# TJMakes_Template.net
KiCad netlist of a schematic drawn in EasyEDA Pro
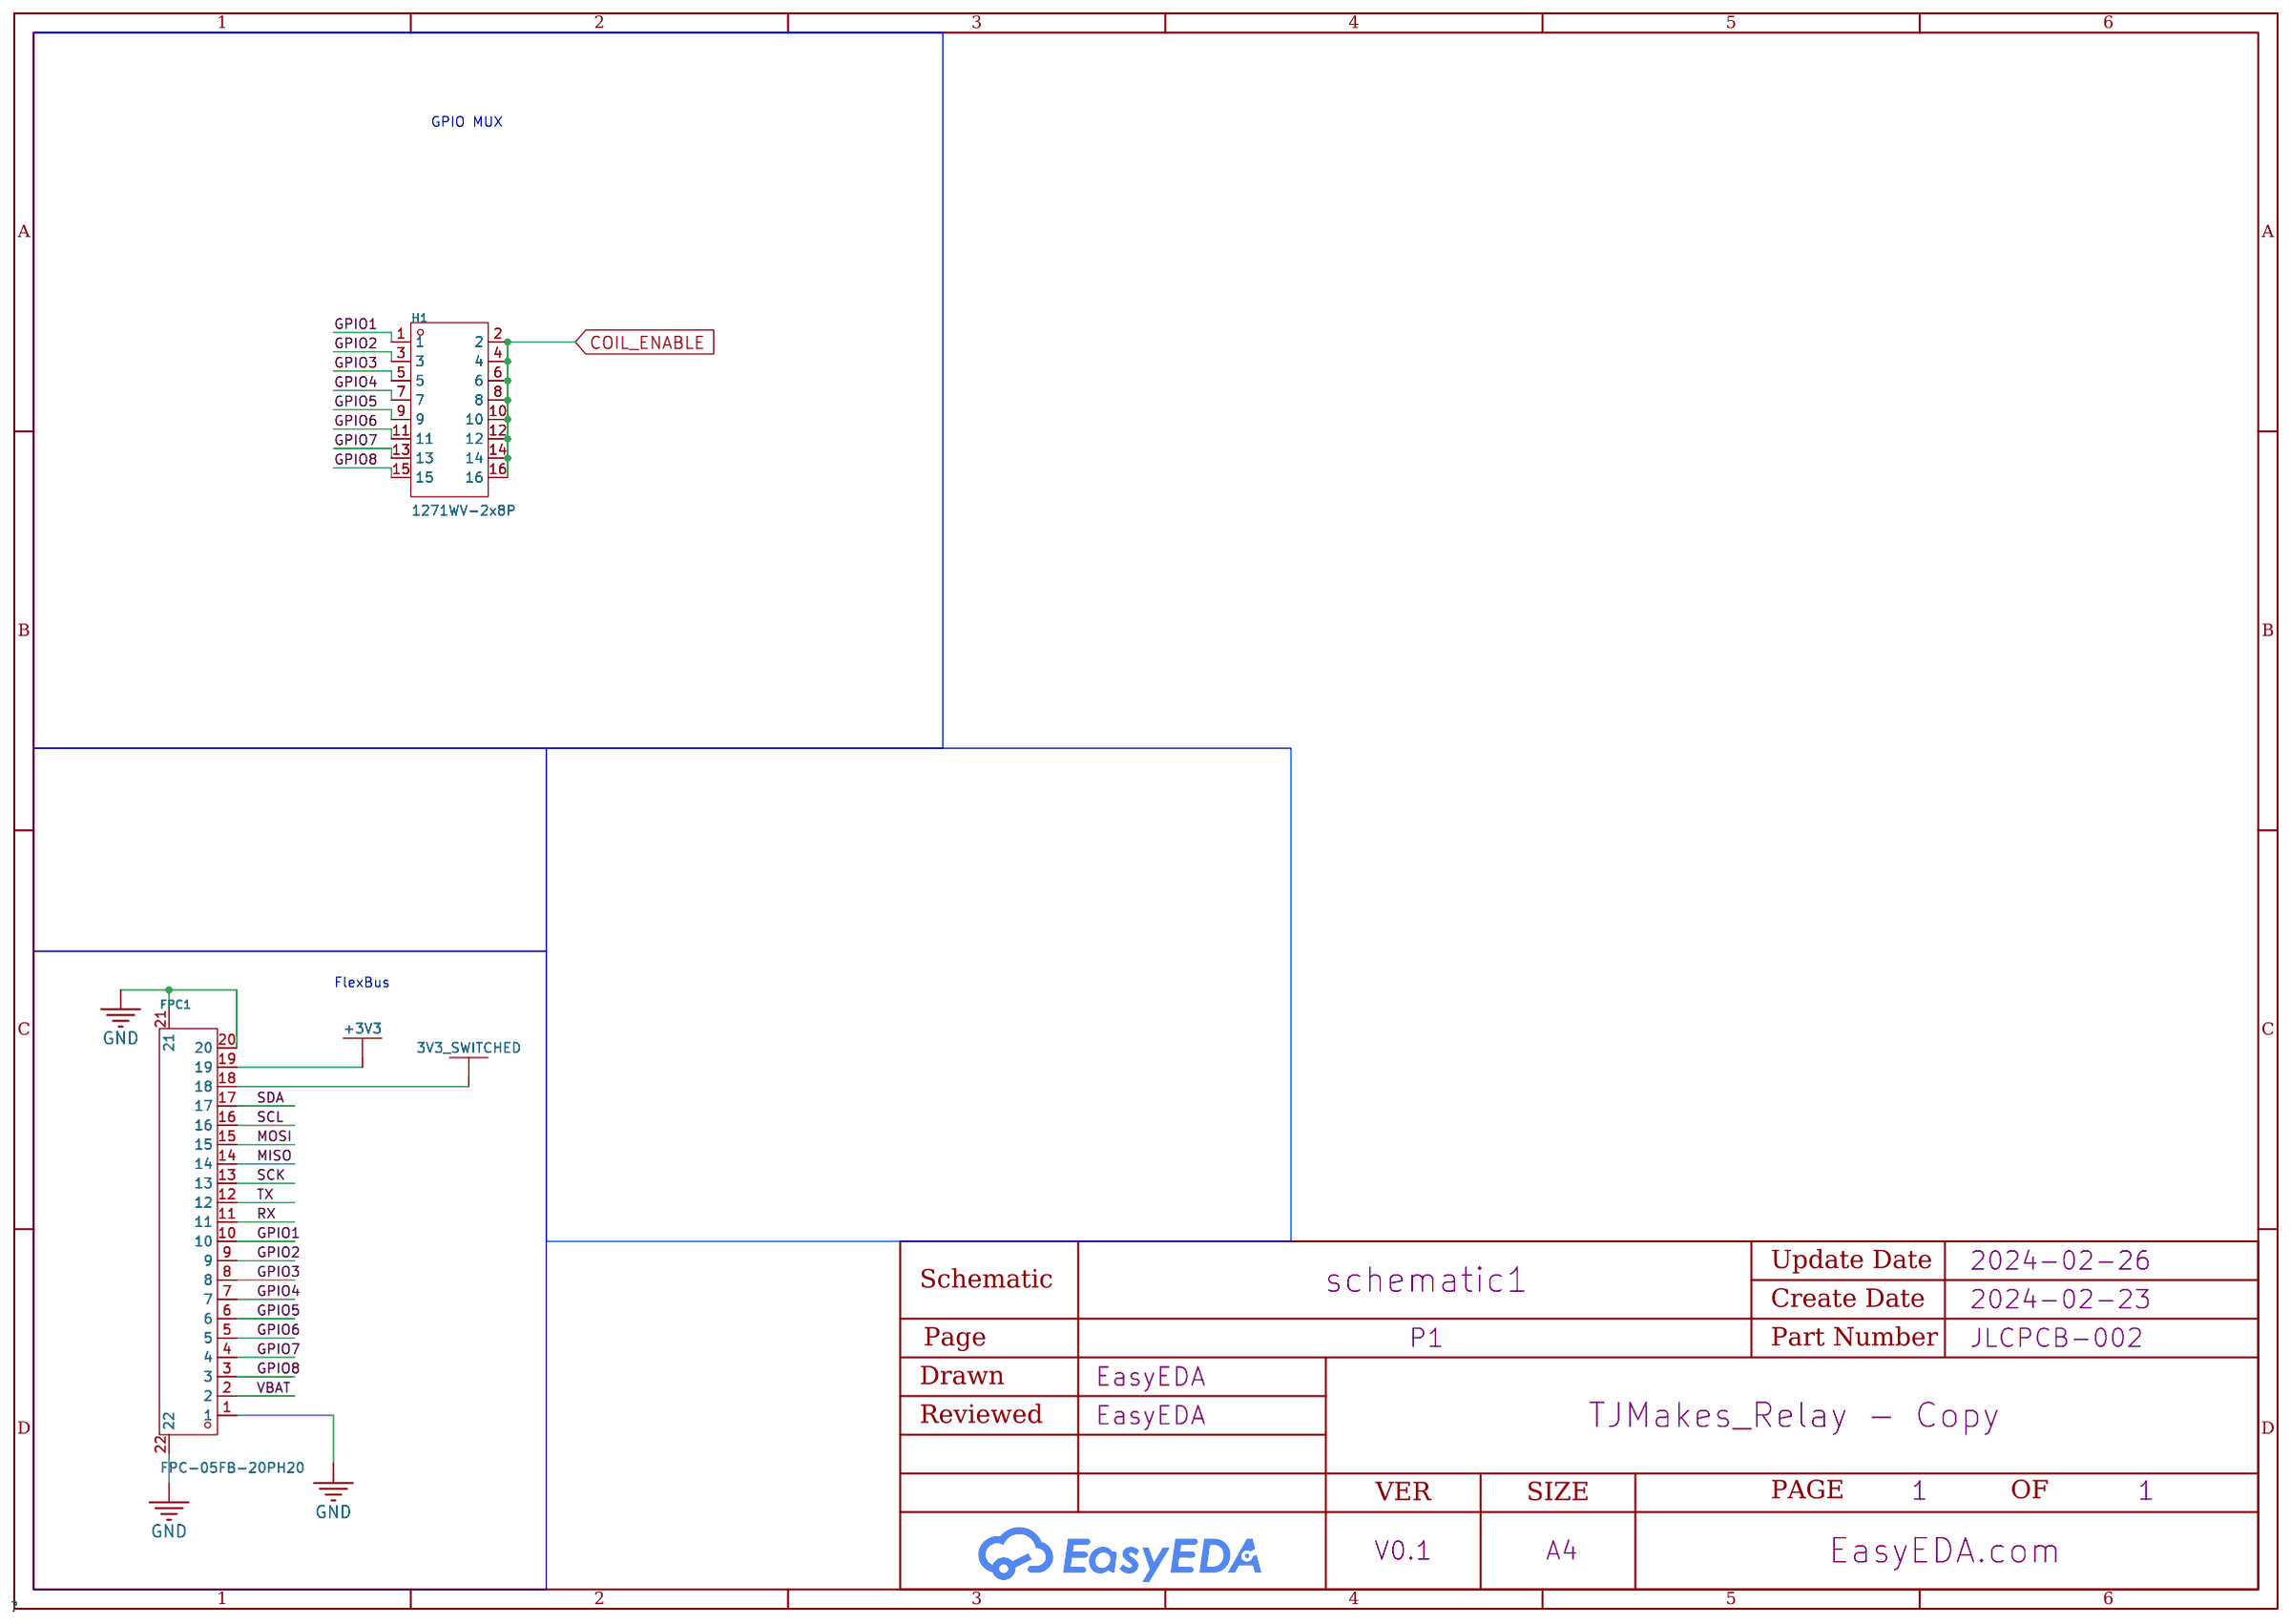
[diagram p0: schematic sheet]

(export (version "E")
  (design (tool "Eeschema 10.0.6"))
  (components
    (comp (ref "FPC1")
      (value "FPC-05FB-20PH20")
      (footprint "easyedapro:FPC-SMD_20P-P0.50_FPC-05FB-20PH20")
      (fields (field (name "Manufacturer") "XUNPU(讯普)"))
      (libsource (lib "easyedapro") (part "FPC-05FB-20PH20"))
    )
    (comp (ref "H1")
      (value "1271WV-2x8P")
      (footprint "easyedapro:HDR-TH_16P-P1.27-V-M-R2-C8-S1.27")
      (fields (field (name "Manufacturer") "kinghelm(金航标)"))
      (libsource (lib "easyedapro") (part "KH-1.27PH180-2X8P-L7.2"))
    )
  )
  (nets
    (net (code "1") (name "+3V3") (class "Default")
      (node (ref "FPC1") (pin "19") (pinfunction "19_19") (pintype "input"))
    )
    (net (code "2") (name "/GPIO1") (class "Default")
      (node (ref "FPC1") (pin "10") (pinfunction "10_10") (pintype "input"))
      (node (ref "H1") (pin "1") (pinfunction "1_1") (pintype "input"))
    )
    (net (code "3") (name "/GPIO2") (class "Default")
      (node (ref "FPC1") (pin "9") (pinfunction "9_9") (pintype "input"))
      (node (ref "H1") (pin "3") (pinfunction "3_3") (pintype "input"))
    )
    (net (code "4") (name "/GPIO3") (class "Default")
      (node (ref "FPC1") (pin "8") (pinfunction "8_8") (pintype "input"))
      (node (ref "H1") (pin "5") (pinfunction "5_5") (pintype "input"))
    )
    (net (code "5") (name "/GPIO4") (class "Default")
      (node (ref "FPC1") (pin "7") (pinfunction "7_7") (pintype "input"))
      (node (ref "H1") (pin "7") (pinfunction "7_7") (pintype "input"))
    )
    (net (code "6") (name "/GPIO5") (class "Default")
      (node (ref "FPC1") (pin "6") (pinfunction "6_6") (pintype "input"))
      (node (ref "H1") (pin "9") (pinfunction "9_9") (pintype "input"))
    )
    (net (code "7") (name "/GPIO6") (class "Default")
      (node (ref "FPC1") (pin "5") (pinfunction "5_5") (pintype "input"))
      (node (ref "H1") (pin "11") (pinfunction "11_11") (pintype "input"))
    )
    (net (code "8") (name "/GPIO7") (class "Default")
      (node (ref "FPC1") (pin "4") (pinfunction "4_4") (pintype "input"))
      (node (ref "H1") (pin "13") (pinfunction "13_13") (pintype "input"))
    )
    (net (code "9") (name "/GPIO8") (class "Default")
      (node (ref "FPC1") (pin "3") (pinfunction "3_3") (pintype "input"))
      (node (ref "H1") (pin "15") (pinfunction "15_15") (pintype "input"))
    )
    (net (code "10") (name "/MISO") (class "Default")
      (node (ref "FPC1") (pin "14") (pinfunction "14_14") (pintype "input"))
    )
    (net (code "11") (name "/MOSI") (class "Default")
      (node (ref "FPC1") (pin "15") (pinfunction "15_15") (pintype "input"))
    )
    (net (code "12") (name "/RX") (class "Default")
      (node (ref "FPC1") (pin "11") (pinfunction "11_11") (pintype "input"))
    )
    (net (code "13") (name "/SCK") (class "Default")
      (node (ref "FPC1") (pin "13") (pinfunction "13_13") (pintype "input"))
    )
    (net (code "14") (name "/SCL") (class "Default")
      (node (ref "FPC1") (pin "16") (pinfunction "16_16") (pintype "input"))
    )
    (net (code "15") (name "/SDA") (class "Default")
      (node (ref "FPC1") (pin "17") (pinfunction "17_17") (pintype "input"))
    )
    (net (code "16") (name "/TX") (class "Default")
      (node (ref "FPC1") (pin "12") (pinfunction "12_12") (pintype "input"))
    )
    (net (code "17") (name "/VBAT") (class "Default")
      (node (ref "FPC1") (pin "2") (pinfunction "2_2") (pintype "input"))
    )
    (net (code "18") (name "3V3_SWITCHED") (class "Default")
      (node (ref "FPC1") (pin "18") (pinfunction "18_18") (pintype "input"))
    )
    (net (code "19") (name "COIL_ENABLE") (class "Default")
      (node (ref "H1") (pin "10") (pinfunction "10_10") (pintype "input"))
      (node (ref "H1") (pin "12") (pinfunction "12_12") (pintype "input"))
      (node (ref "H1") (pin "14") (pinfunction "14_14") (pintype "input"))
      (node (ref "H1") (pin "16") (pinfunction "16_16") (pintype "input"))
      (node (ref "H1") (pin "2") (pinfunction "2_2") (pintype "input"))
      (node (ref "H1") (pin "4") (pinfunction "4_4") (pintype "input"))
      (node (ref "H1") (pin "6") (pinfunction "6_6") (pintype "input"))
      (node (ref "H1") (pin "8") (pinfunction "8_8") (pintype "input"))
    )
    (net (code "20") (name "GND") (class "Default")
      (node (ref "FPC1") (pin "1") (pinfunction "1_1") (pintype "input"))
      (node (ref "FPC1") (pin "20") (pinfunction "20_20") (pintype "input"))
      (node (ref "FPC1") (pin "21") (pinfunction "21_21") (pintype "input"))
      (node (ref "FPC1") (pin "22") (pinfunction "22_22") (pintype "input"))
    )
  )
)
